# esp32_plus.net
KiCad netlist of a schematic drawn in EAGLE
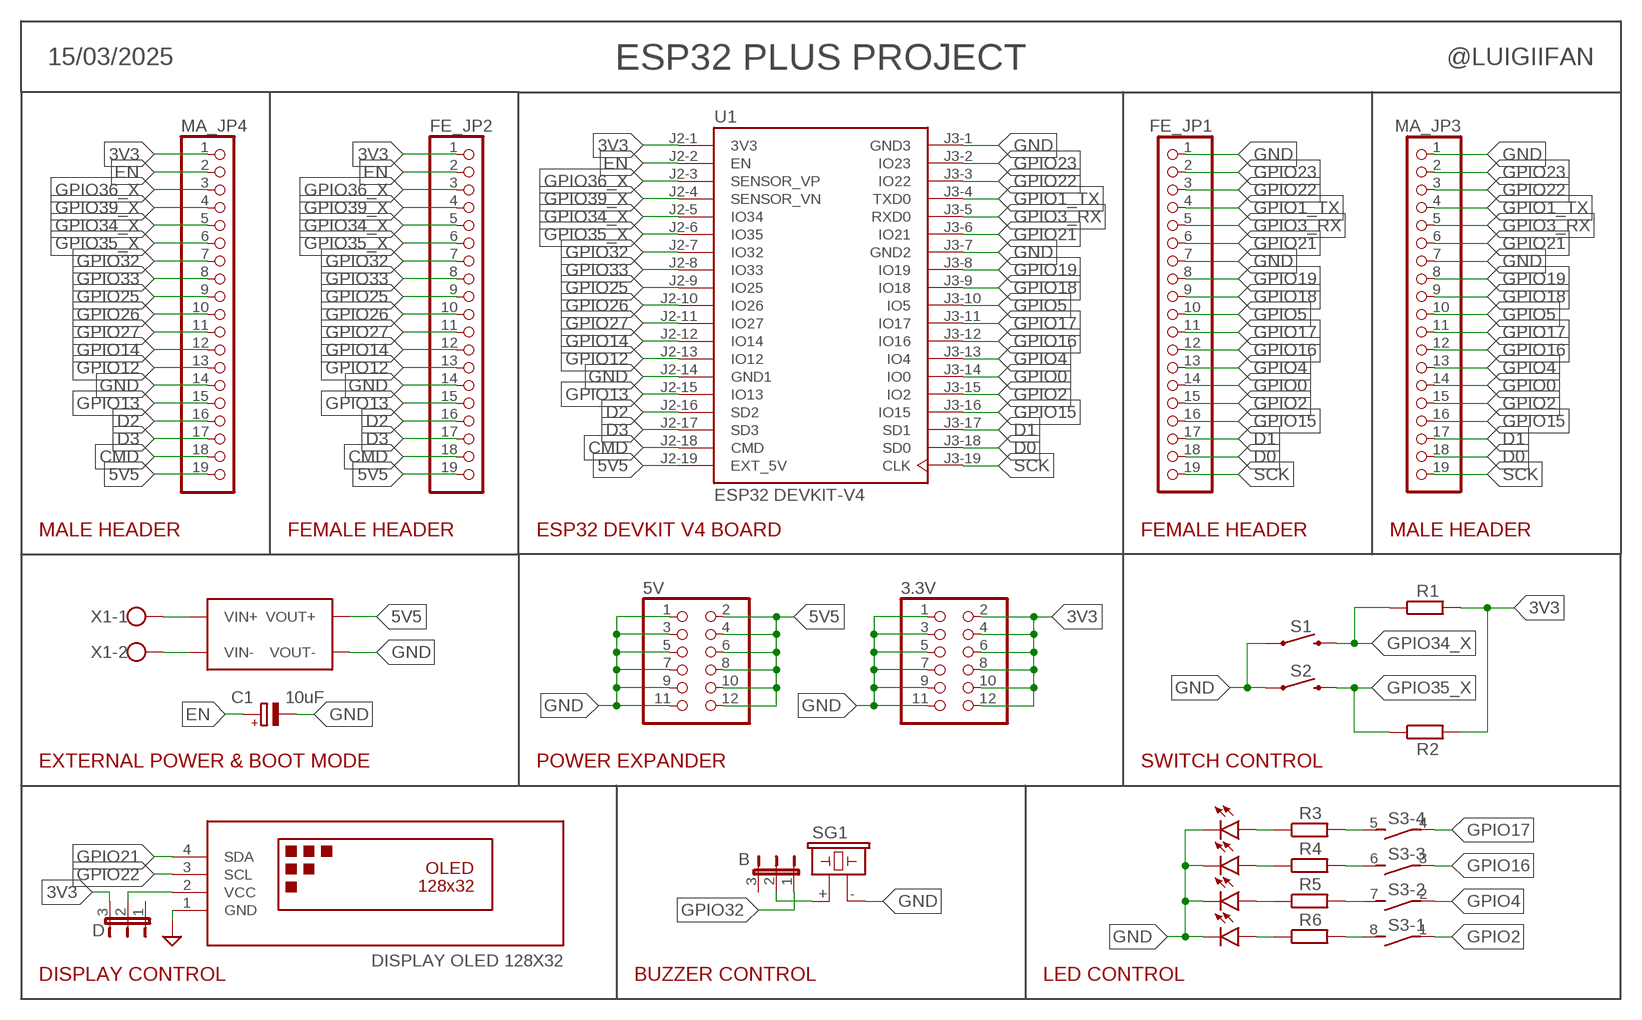
[diagram p0: schematic, sheet 1]

(export (version "E")
  (design (tool "Eeschema 10.0.6"))
  (components
    (comp (ref "3.3V")
      (value "PINHD-2X6")
      (footprint "eagle-import:2X06")
      (libsource (lib "eagle-import") (part "PINHD-2X6"))
    )
    (comp (ref "5V")
      (value "PINHD-2X6")
      (footprint "eagle-import:2X06")
      (libsource (lib "eagle-import") (part "PINHD-2X6"))
    )
    (comp (ref "B")
      (value "JP2E")
      (footprint "eagle-import:JP2")
      (libsource (lib "eagle-import") (part "JP2E"))
    )
    (comp (ref "C1")
      (value "10uF")
      (footprint "eagle-import:E2,5-5")
      (libsource (lib "eagle-import") (part "CPOL-EUE2.5-5"))
    )
    (comp (ref "D")
      (value "JP2E")
      (footprint "eagle-import:JP2")
      (libsource (lib "eagle-import") (part "JP2E"))
    )
    (comp (ref "FE_JP1")
      (value "PINHD-1X19")
      (footprint "eagle-import:1X19")
      (libsource (lib "eagle-import") (part "PINHD-1X19"))
    )
    (comp (ref "FE_JP2")
      (value "PINHD-1X19")
      (footprint "eagle-import:1X19")
      (libsource (lib "eagle-import") (part "PINHD-1X19"))
    )
    (comp (ref "L1")
      (value "LED3MM")
      (footprint "eagle-import:LED3MM")
      (fields (field (name "SPICEPREFIX") "L"))
      (libsource (lib "eagle-import") (part "LED3MM"))
    )
    (comp (ref "L2")
      (value "LED3MM")
      (footprint "eagle-import:LED3MM")
      (libsource (lib "eagle-import") (part "LED3MM"))
    )
    (comp (ref "L3")
      (value "LED3MM")
      (footprint "eagle-import:LED3MM")
      (libsource (lib "eagle-import") (part "LED3MM"))
    )
    (comp (ref "L4")
      (value "LED3MM")
      (footprint "eagle-import:LED3MM")
      (libsource (lib "eagle-import") (part "LED3MM"))
    )
    (comp (ref "MA_JP3")
      (value "PINHD-1X19")
      (footprint "eagle-import:1X19")
      (libsource (lib "eagle-import") (part "PINHD-1X19"))
    )
    (comp (ref "MA_JP4")
      (value "PINHD-1X19")
      (footprint "eagle-import:1X19")
      (libsource (lib "eagle-import") (part "PINHD-1X19"))
    )
    (comp (ref "MP1584")
      (value "MP1584")
      (footprint "eagle-import:DC-BRICK")
      (libsource (lib "eagle-import") (part "MP1584"))
    )
    (comp (ref "R1")
      (value "R-EU_0207/10")
      (footprint "eagle-import:0207_10")
      (libsource (lib "eagle-import") (part "R-EU_0207/10"))
    )
    (comp (ref "R2")
      (value "R-EU_0207/10")
      (footprint "eagle-import:0207_10")
      (libsource (lib "eagle-import") (part "R-EU_0207/10"))
    )
    (comp (ref "R3")
      (value "R-EU_0207/10")
      (footprint "eagle-import:0207_10")
      (libsource (lib "eagle-import") (part "R-EU_0207/10"))
    )
    (comp (ref "R4")
      (value "R-EU_0207/10")
      (footprint "eagle-import:0207_10")
      (libsource (lib "eagle-import") (part "R-EU_0207/10"))
    )
    (comp (ref "R5")
      (value "R-EU_0207/10")
      (footprint "eagle-import:0207_10")
      (libsource (lib "eagle-import") (part "R-EU_0207/10"))
    )
    (comp (ref "R6")
      (value "R-EU_0207/10")
      (footprint "eagle-import:0207_10")
      (libsource (lib "eagle-import") (part "R-EU_0207/10"))
    )
    (comp (ref "S1")
      (value "MOMENTARY-SWITCH-SPST-PTH-6.0MM")
      (footprint "eagle-import:TACTILE_SWITCH_PTH_6.0MM")
      (libsource (lib "eagle-import") (part "MOMENTARY-SWITCH-SPST-PTH-6.0MM"))
    )
    (comp (ref "S2")
      (value "MOMENTARY-SWITCH-SPST-PTH-6.0MM")
      (footprint "eagle-import:TACTILE_SWITCH_PTH_6.0MM")
      (libsource (lib "eagle-import") (part "MOMENTARY-SWITCH-SPST-PTH-6.0MM"))
    )
    (comp (ref "S3")
      (value "DS04E")
      (footprint "eagle-import:DS-04")
      (libsource (lib "eagle-import") (part "DS04E"))
    )
    (comp (ref "SG1")
      (value "F/CM12P")
      (footprint "eagle-import:F_CM12P")
      (libsource (lib "eagle-import") (part "F/CM12P"))
    )
    (comp (ref "U$1")
      (value "DISPLAY OLED 128X32")
      (footprint "eagle-import:DISPLAY-OLED-128X32")
      (libsource (lib "eagle-import") (part "DISPLAY-OLED-128X32"))
    )
    (comp (ref "U1")
      (value "ESP32 DEVKIT-V4")
      (footprint "eagle-import:MODULE_ESP32-DEVKITC-32D")
      (fields (field (name "MF") "Espressif Systems") (field (name "MP") "ESP32-DEVKITC-32D"))
      (libsource (lib "eagle-import") (part "ESP32-DEVKITC-32D"))
    )
    (comp (ref "X1")
      (value "W237-102")
      (footprint "eagle-import:W237-102")
      (fields (field (name "MPN") "237-102"))
      (libsource (lib "eagle-import") (part "W237-102"))
    )
  )
  (nets
    (net (code "1") (name "3V3") (class "Default")
      (node (ref "3.3V") (pin "10") (pinfunction "10_10") (pintype "passive"))
      (node (ref "3.3V") (pin "12") (pinfunction "12_12") (pintype "passive"))
      (node (ref "3.3V") (pin "2") (pinfunction "2_2") (pintype "passive"))
      (node (ref "3.3V") (pin "4") (pinfunction "4_4") (pintype "passive"))
      (node (ref "3.3V") (pin "6") (pinfunction "6_6") (pintype "passive"))
      (node (ref "3.3V") (pin "8") (pinfunction "8_8") (pintype "passive"))
      (node (ref "D") (pin "3") (pinfunction "3_3") (pintype "passive"))
      (node (ref "FE_JP2") (pin "1") (pinfunction "1_1") (pintype "passive"))
      (node (ref "MA_JP4") (pin "1") (pinfunction "1_1") (pintype "passive"))
      (node (ref "R1") (pin "2") (pinfunction "2_2") (pintype "passive"))
      (node (ref "R2") (pin "2") (pinfunction "2_2") (pintype "passive"))
      (node (ref "U1") (pin "J2-1") (pinfunction "3V3_J2-1") (pintype "power_in"))
    )
    (net (code "2") (name "5V5") (class "Default")
      (node (ref "5V") (pin "10") (pinfunction "10_10") (pintype "passive"))
      (node (ref "5V") (pin "12") (pinfunction "12_12") (pintype "passive"))
      (node (ref "5V") (pin "2") (pinfunction "2_2") (pintype "passive"))
      (node (ref "5V") (pin "4") (pinfunction "4_4") (pintype "passive"))
      (node (ref "5V") (pin "6") (pinfunction "6_6") (pintype "passive"))
      (node (ref "5V") (pin "8") (pinfunction "8_8") (pintype "passive"))
      (node (ref "FE_JP2") (pin "19") (pinfunction "19_19") (pintype "passive"))
      (node (ref "MA_JP4") (pin "19") (pinfunction "19_19") (pintype "passive"))
      (node (ref "MP1584") (pin "OUT1+") (pinfunction "VOUT+_OUT1+") (pintype "output"))
      (node (ref "MP1584") (pin "OUT2+") (pinfunction "VOUT+_OUT2+") (pintype "output"))
      (node (ref "U1") (pin "J2-19") (pinfunction "EXT_5V_J2-19") (pintype "power_in"))
    )
    (net (code "3") (name "CMD") (class "Default")
      (node (ref "FE_JP2") (pin "18") (pinfunction "18_18") (pintype "passive"))
      (node (ref "MA_JP4") (pin "18") (pinfunction "18_18") (pintype "passive"))
      (node (ref "U1") (pin "J2-18") (pinfunction "CMD_J2-18") (pintype "bidirectional"))
    )
    (net (code "4") (name "D0") (class "Default")
      (node (ref "FE_JP1") (pin "18") (pinfunction "18_18") (pintype "passive"))
      (node (ref "MA_JP3") (pin "18") (pinfunction "18_18") (pintype "passive"))
      (node (ref "U1") (pin "J3-18") (pinfunction "SD0_J3-18") (pintype "bidirectional"))
    )
    (net (code "5") (name "D1") (class "Default")
      (node (ref "FE_JP1") (pin "17") (pinfunction "17_17") (pintype "passive"))
      (node (ref "MA_JP3") (pin "17") (pinfunction "17_17") (pintype "passive"))
      (node (ref "U1") (pin "J3-17") (pinfunction "SD1_J3-17") (pintype "bidirectional"))
    )
    (net (code "6") (name "D2") (class "Default")
      (node (ref "FE_JP2") (pin "16") (pinfunction "16_16") (pintype "passive"))
      (node (ref "MA_JP4") (pin "16") (pinfunction "16_16") (pintype "passive"))
      (node (ref "U1") (pin "J2-16") (pinfunction "SD2_J2-16") (pintype "bidirectional"))
    )
    (net (code "7") (name "D3") (class "Default")
      (node (ref "FE_JP2") (pin "17") (pinfunction "17_17") (pintype "passive"))
      (node (ref "MA_JP4") (pin "17") (pinfunction "17_17") (pintype "passive"))
      (node (ref "U1") (pin "J2-17") (pinfunction "SD3_J2-17") (pintype "bidirectional"))
    )
    (net (code "8") (name "EN") (class "Default")
      (node (ref "C1") (pin "+") (pinfunction "+_+") (pintype "passive"))
      (node (ref "FE_JP2") (pin "2") (pinfunction "2_2") (pintype "passive"))
      (node (ref "MA_JP4") (pin "2") (pinfunction "2_2") (pintype "passive"))
      (node (ref "U1") (pin "J2-2") (pinfunction "EN_J2-2") (pintype "input"))
    )
    (net (code "9") (name "GND") (class "Default")
      (node (ref "3.3V") (pin "1") (pinfunction "1_1") (pintype "passive"))
      (node (ref "3.3V") (pin "11") (pinfunction "11_11") (pintype "passive"))
      (node (ref "3.3V") (pin "3") (pinfunction "3_3") (pintype "passive"))
      (node (ref "3.3V") (pin "5") (pinfunction "5_5") (pintype "passive"))
      (node (ref "3.3V") (pin "7") (pinfunction "7_7") (pintype "passive"))
      (node (ref "3.3V") (pin "9") (pinfunction "9_9") (pintype "passive"))
      (node (ref "5V") (pin "1") (pinfunction "1_1") (pintype "passive"))
      (node (ref "5V") (pin "11") (pinfunction "11_11") (pintype "passive"))
      (node (ref "5V") (pin "3") (pinfunction "3_3") (pintype "passive"))
      (node (ref "5V") (pin "5") (pinfunction "5_5") (pintype "passive"))
      (node (ref "5V") (pin "7") (pinfunction "7_7") (pintype "passive"))
      (node (ref "5V") (pin "9") (pinfunction "9_9") (pintype "passive"))
      (node (ref "C1") (pin "-") (pinfunction "-_-") (pintype "passive"))
      (node (ref "FE_JP1") (pin "1") (pinfunction "1_1") (pintype "passive"))
      (node (ref "FE_JP1") (pin "7") (pinfunction "7_7") (pintype "passive"))
      (node (ref "FE_JP2") (pin "14") (pinfunction "14_14") (pintype "passive"))
      (node (ref "L1") (pin "K") (pinfunction "C_K") (pintype "passive"))
      (node (ref "L2") (pin "K") (pinfunction "C_K") (pintype "passive"))
      (node (ref "L3") (pin "K") (pinfunction "C_K") (pintype "passive"))
      (node (ref "L4") (pin "K") (pinfunction "C_K") (pintype "passive"))
      (node (ref "MA_JP3") (pin "1") (pinfunction "1_1") (pintype "passive"))
      (node (ref "MA_JP3") (pin "7") (pinfunction "7_7") (pintype "passive"))
      (node (ref "MA_JP4") (pin "14") (pinfunction "14_14") (pintype "passive"))
      (node (ref "MP1584") (pin "OUT1-") (pinfunction "VOUT-_OUT1-") (pintype "output"))
      (node (ref "MP1584") (pin "OUT2-") (pinfunction "VOUT-_OUT2-") (pintype "output"))
      (node (ref "S1") (pin "1") (pinfunction "1_1") (pintype "passive"))
      (node (ref "S2") (pin "1") (pinfunction "1_1") (pintype "passive"))
      (node (ref "SG1") (pin "-") (pinfunction "2_-") (pintype "passive"))
      (node (ref "U$1") (pin "1") (pinfunction "GND_1") (pintype "power_in"))
      (node (ref "U1") (pin "J2-14") (pinfunction "GND1_J2-14") (pintype "power_in"))
      (node (ref "U1") (pin "J3-1") (pinfunction "GND3_J3-1") (pintype "power_in"))
      (node (ref "U1") (pin "J3-7") (pinfunction "GND2_J3-7") (pintype "power_in"))
    )
    (net (code "10") (name "GPIO0") (class "Default")
      (node (ref "FE_JP1") (pin "14") (pinfunction "14_14") (pintype "passive"))
      (node (ref "MA_JP3") (pin "14") (pinfunction "14_14") (pintype "passive"))
      (node (ref "U1") (pin "J3-14") (pinfunction "IO0_J3-14") (pintype "bidirectional"))
    )
    (net (code "11") (name "GPIO1_TX") (class "Default")
      (node (ref "FE_JP1") (pin "4") (pinfunction "4_4") (pintype "passive"))
      (node (ref "MA_JP3") (pin "4") (pinfunction "4_4") (pintype "passive"))
      (node (ref "U1") (pin "J3-4") (pinfunction "TXD0_J3-4") (pintype "output"))
    )
    (net (code "12") (name "GPIO2") (class "Default")
      (node (ref "FE_JP1") (pin "15") (pinfunction "15_15") (pintype "passive"))
      (node (ref "MA_JP3") (pin "15") (pinfunction "15_15") (pintype "passive"))
      (node (ref "S3") (pin "1") (pinfunction "1_1") (pintype "passive"))
      (node (ref "U1") (pin "J3-15") (pinfunction "IO2_J3-15") (pintype "bidirectional"))
    )
    (net (code "13") (name "GPIO3_RX") (class "Default")
      (node (ref "FE_JP1") (pin "5") (pinfunction "5_5") (pintype "passive"))
      (node (ref "MA_JP3") (pin "5") (pinfunction "5_5") (pintype "passive"))
      (node (ref "U1") (pin "J3-5") (pinfunction "RXD0_J3-5") (pintype "input"))
    )
    (net (code "14") (name "GPIO4") (class "Default")
      (node (ref "FE_JP1") (pin "13") (pinfunction "13_13") (pintype "passive"))
      (node (ref "MA_JP3") (pin "13") (pinfunction "13_13") (pintype "passive"))
      (node (ref "S3") (pin "2") (pinfunction "1_2") (pintype "passive"))
      (node (ref "U1") (pin "J3-13") (pinfunction "IO4_J3-13") (pintype "bidirectional"))
    )
    (net (code "15") (name "GPIO5") (class "Default")
      (node (ref "FE_JP1") (pin "10") (pinfunction "10_10") (pintype "passive"))
      (node (ref "MA_JP3") (pin "10") (pinfunction "10_10") (pintype "passive"))
      (node (ref "U1") (pin "J3-10") (pinfunction "IO5_J3-10") (pintype "bidirectional"))
    )
    (net (code "16") (name "GPIO12") (class "Default")
      (node (ref "FE_JP2") (pin "13") (pinfunction "13_13") (pintype "passive"))
      (node (ref "MA_JP4") (pin "13") (pinfunction "13_13") (pintype "passive"))
      (node (ref "U1") (pin "J2-13") (pinfunction "IO12_J2-13") (pintype "bidirectional"))
    )
    (net (code "17") (name "GPIO13") (class "Default")
      (node (ref "FE_JP2") (pin "15") (pinfunction "15_15") (pintype "passive"))
      (node (ref "MA_JP4") (pin "15") (pinfunction "15_15") (pintype "passive"))
      (node (ref "U1") (pin "J2-15") (pinfunction "IO13_J2-15") (pintype "bidirectional"))
    )
    (net (code "18") (name "GPIO14") (class "Default")
      (node (ref "FE_JP2") (pin "12") (pinfunction "12_12") (pintype "passive"))
      (node (ref "MA_JP4") (pin "12") (pinfunction "12_12") (pintype "passive"))
      (node (ref "U1") (pin "J2-12") (pinfunction "IO14_J2-12") (pintype "bidirectional"))
    )
    (net (code "19") (name "GPIO15") (class "Default")
      (node (ref "FE_JP1") (pin "16") (pinfunction "16_16") (pintype "passive"))
      (node (ref "MA_JP3") (pin "16") (pinfunction "16_16") (pintype "passive"))
      (node (ref "U1") (pin "J3-16") (pinfunction "IO15_J3-16") (pintype "bidirectional"))
    )
    (net (code "20") (name "GPIO16") (class "Default")
      (node (ref "FE_JP1") (pin "12") (pinfunction "12_12") (pintype "passive"))
      (node (ref "MA_JP3") (pin "12") (pinfunction "12_12") (pintype "passive"))
      (node (ref "S3") (pin "3") (pinfunction "1_3") (pintype "passive"))
      (node (ref "U1") (pin "J3-12") (pinfunction "IO16_J3-12") (pintype "bidirectional"))
    )
    (net (code "21") (name "GPIO17") (class "Default")
      (node (ref "FE_JP1") (pin "11") (pinfunction "11_11") (pintype "passive"))
      (node (ref "MA_JP3") (pin "11") (pinfunction "11_11") (pintype "passive"))
      (node (ref "S3") (pin "4") (pinfunction "1_4") (pintype "passive"))
      (node (ref "U1") (pin "J3-11") (pinfunction "IO17_J3-11") (pintype "bidirectional"))
    )
    (net (code "22") (name "GPIO18") (class "Default")
      (node (ref "FE_JP1") (pin "9") (pinfunction "9_9") (pintype "passive"))
      (node (ref "MA_JP3") (pin "9") (pinfunction "9_9") (pintype "passive"))
      (node (ref "U1") (pin "J3-9") (pinfunction "IO18_J3-9") (pintype "bidirectional"))
    )
    (net (code "23") (name "GPIO19") (class "Default")
      (node (ref "FE_JP1") (pin "8") (pinfunction "8_8") (pintype "passive"))
      (node (ref "MA_JP3") (pin "8") (pinfunction "8_8") (pintype "passive"))
      (node (ref "U1") (pin "J3-8") (pinfunction "IO19_J3-8") (pintype "bidirectional"))
    )
    (net (code "24") (name "GPIO21") (class "Default")
      (node (ref "FE_JP1") (pin "6") (pinfunction "6_6") (pintype "passive"))
      (node (ref "MA_JP3") (pin "6") (pinfunction "6_6") (pintype "passive"))
      (node (ref "U$1") (pin "4") (pinfunction "SDA_4") (pintype "bidirectional"))
      (node (ref "U1") (pin "J3-6") (pinfunction "IO21_J3-6") (pintype "bidirectional"))
    )
    (net (code "25") (name "GPIO22") (class "Default")
      (node (ref "FE_JP1") (pin "3") (pinfunction "3_3") (pintype "passive"))
      (node (ref "MA_JP3") (pin "3") (pinfunction "3_3") (pintype "passive"))
      (node (ref "U$1") (pin "3") (pinfunction "SCL_3") (pintype "bidirectional"))
      (node (ref "U1") (pin "J3-3") (pinfunction "IO22_J3-3") (pintype "bidirectional"))
    )
    (net (code "26") (name "GPIO23") (class "Default")
      (node (ref "FE_JP1") (pin "2") (pinfunction "2_2") (pintype "passive"))
      (node (ref "MA_JP3") (pin "2") (pinfunction "2_2") (pintype "passive"))
      (node (ref "U1") (pin "J3-2") (pinfunction "IO23_J3-2") (pintype "bidirectional"))
    )
    (net (code "27") (name "GPIO25") (class "Default")
      (node (ref "FE_JP2") (pin "9") (pinfunction "9_9") (pintype "passive"))
      (node (ref "MA_JP4") (pin "9") (pinfunction "9_9") (pintype "passive"))
      (node (ref "U1") (pin "J2-9") (pinfunction "IO25_J2-9") (pintype "bidirectional"))
    )
    (net (code "28") (name "GPIO26") (class "Default")
      (node (ref "FE_JP2") (pin "10") (pinfunction "10_10") (pintype "passive"))
      (node (ref "MA_JP4") (pin "10") (pinfunction "10_10") (pintype "passive"))
      (node (ref "U1") (pin "J2-10") (pinfunction "IO26_J2-10") (pintype "bidirectional"))
    )
    (net (code "29") (name "GPIO27") (class "Default")
      (node (ref "FE_JP2") (pin "11") (pinfunction "11_11") (pintype "passive"))
      (node (ref "MA_JP4") (pin "11") (pinfunction "11_11") (pintype "passive"))
      (node (ref "U1") (pin "J2-11") (pinfunction "IO27_J2-11") (pintype "bidirectional"))
    )
    (net (code "30") (name "GPIO32") (class "Default")
      (node (ref "B") (pin "1") (pinfunction "1_1") (pintype "passive"))
      (node (ref "FE_JP2") (pin "7") (pinfunction "7_7") (pintype "passive"))
      (node (ref "MA_JP4") (pin "7") (pinfunction "7_7") (pintype "passive"))
      (node (ref "U1") (pin "J2-7") (pinfunction "IO32_J2-7") (pintype "bidirectional"))
    )
    (net (code "31") (name "GPIO33") (class "Default")
      (node (ref "FE_JP2") (pin "8") (pinfunction "8_8") (pintype "passive"))
      (node (ref "MA_JP4") (pin "8") (pinfunction "8_8") (pintype "passive"))
      (node (ref "U1") (pin "J2-8") (pinfunction "IO33_J2-8") (pintype "bidirectional"))
    )
    (net (code "32") (name "GPIO34_X") (class "Default")
      (node (ref "FE_JP2") (pin "5") (pinfunction "5_5") (pintype "passive"))
      (node (ref "MA_JP4") (pin "5") (pinfunction "5_5") (pintype "passive"))
      (node (ref "R1") (pin "1") (pinfunction "1_1") (pintype "passive"))
      (node (ref "S1") (pin "4") (pinfunction "2_4") (pintype "passive"))
      (node (ref "U1") (pin "J2-5") (pinfunction "IO34_J2-5") (pintype "bidirectional"))
    )
    (net (code "33") (name "GPIO35_X") (class "Default")
      (node (ref "FE_JP2") (pin "6") (pinfunction "6_6") (pintype "passive"))
      (node (ref "MA_JP4") (pin "6") (pinfunction "6_6") (pintype "passive"))
      (node (ref "R2") (pin "1") (pinfunction "1_1") (pintype "passive"))
      (node (ref "S2") (pin "4") (pinfunction "2_4") (pintype "passive"))
      (node (ref "U1") (pin "J2-6") (pinfunction "IO35_J2-6") (pintype "bidirectional"))
    )
    (net (code "34") (name "GPIO36_X") (class "Default")
      (node (ref "FE_JP2") (pin "3") (pinfunction "3_3") (pintype "passive"))
      (node (ref "MA_JP4") (pin "3") (pinfunction "3_3") (pintype "passive"))
      (node (ref "U1") (pin "J2-3") (pinfunction "SENSOR_VP_J2-3") (pintype "input"))
    )
    (net (code "35") (name "GPIO39_X") (class "Default")
      (node (ref "FE_JP2") (pin "4") (pinfunction "4_4") (pintype "passive"))
      (node (ref "MA_JP4") (pin "4") (pinfunction "4_4") (pintype "passive"))
      (node (ref "U1") (pin "J2-4") (pinfunction "SENSOR_VN_J2-4") (pintype "input"))
    )
    (net (code "36") (name "Net-(L1-PadA)") (class "Default")
      (node (ref "L1") (pin "A") (pinfunction "A_A") (pintype "passive"))
      (node (ref "R3") (pin "1") (pinfunction "1_1") (pintype "passive"))
    )
    (net (code "37") (name "Net-(L2-PadA)") (class "Default")
      (node (ref "L2") (pin "A") (pinfunction "A_A") (pintype "passive"))
      (node (ref "R4") (pin "1") (pinfunction "1_1") (pintype "passive"))
    )
    (net (code "38") (name "Net-(L3-PadA)") (class "Default")
      (node (ref "L3") (pin "A") (pinfunction "A_A") (pintype "passive"))
      (node (ref "R5") (pin "1") (pinfunction "1_1") (pintype "passive"))
    )
    (net (code "39") (name "Net-(L4-PadA)") (class "Default")
      (node (ref "L4") (pin "A") (pinfunction "A_A") (pintype "passive"))
      (node (ref "R6") (pin "1") (pinfunction "1_1") (pintype "passive"))
    )
    (net (code "40") (name "Net-(S3A-2)") (class "Default")
      (node (ref "R6") (pin "2") (pinfunction "2_2") (pintype "passive"))
      (node (ref "S3") (pin "8") (pinfunction "2_8") (pintype "passive"))
    )
    (net (code "41") (name "Net-(S3B-2)") (class "Default")
      (node (ref "R5") (pin "2") (pinfunction "2_2") (pintype "passive"))
      (node (ref "S3") (pin "7") (pinfunction "2_7") (pintype "passive"))
    )
    (net (code "42") (name "Net-(S3C-2)") (class "Default")
      (node (ref "R4") (pin "2") (pinfunction "2_2") (pintype "passive"))
      (node (ref "S3") (pin "6") (pinfunction "2_6") (pintype "passive"))
    )
    (net (code "43") (name "Net-(S3D-2)") (class "Default")
      (node (ref "R3") (pin "2") (pinfunction "2_2") (pintype "passive"))
      (node (ref "S3") (pin "5") (pinfunction "2_5") (pintype "passive"))
    )
    (net (code "44") (name "Net-(SG1-1)") (class "Default")
      (node (ref "B") (pin "2") (pinfunction "2_2") (pintype "passive"))
      (node (ref "SG1") (pin "+") (pinfunction "1_+") (pintype "passive"))
    )
    (net (code "45") (name "Net-(U$1-VCC)") (class "Default")
      (node (ref "D") (pin "2") (pinfunction "2_2") (pintype "passive"))
      (node (ref "U$1") (pin "2") (pinfunction "VCC_2") (pintype "power_in"))
    )
    (net (code "46") (name "Net-(X1A-KL)") (class "Default")
      (node (ref "MP1584") (pin "IN1+") (pinfunction "VIN+_IN1+") (pintype "input"))
      (node (ref "MP1584") (pin "IN2+") (pinfunction "VIN+_IN2+") (pintype "input"))
      (node (ref "X1") (pin "1") (pinfunction "KL_1") (pintype "passive"))
    )
    (net (code "47") (name "Net-(X1B-KL)") (class "Default")
      (node (ref "MP1584") (pin "IN1-") (pinfunction "VIN-_IN1-") (pintype "input"))
      (node (ref "MP1584") (pin "IN2-") (pinfunction "VIN-_IN2-") (pintype "input"))
      (node (ref "X1") (pin "2") (pinfunction "KL_2") (pintype "passive"))
    )
    (net (code "48") (name "SCK") (class "Default")
      (node (ref "FE_JP1") (pin "19") (pinfunction "19_19") (pintype "passive"))
      (node (ref "MA_JP3") (pin "19") (pinfunction "19_19") (pintype "passive"))
      (node (ref "U1") (pin "J3-19") (pinfunction "CLK_J3-19") (pintype "input"))
    )
    (net (code "49") (name "unconnected-(B-Pad3)") (class "Default")
      (node (ref "B") (pin "3") (pinfunction "3_3") (pintype "passive"))
    )
    (net (code "50") (name "unconnected-(D-Pad1)") (class "Default")
      (node (ref "D") (pin "1") (pinfunction "1_1") (pintype "passive"))
    )
  )
)
